# output.net
KiCad netlist of a schematic drawn in Altium Designer
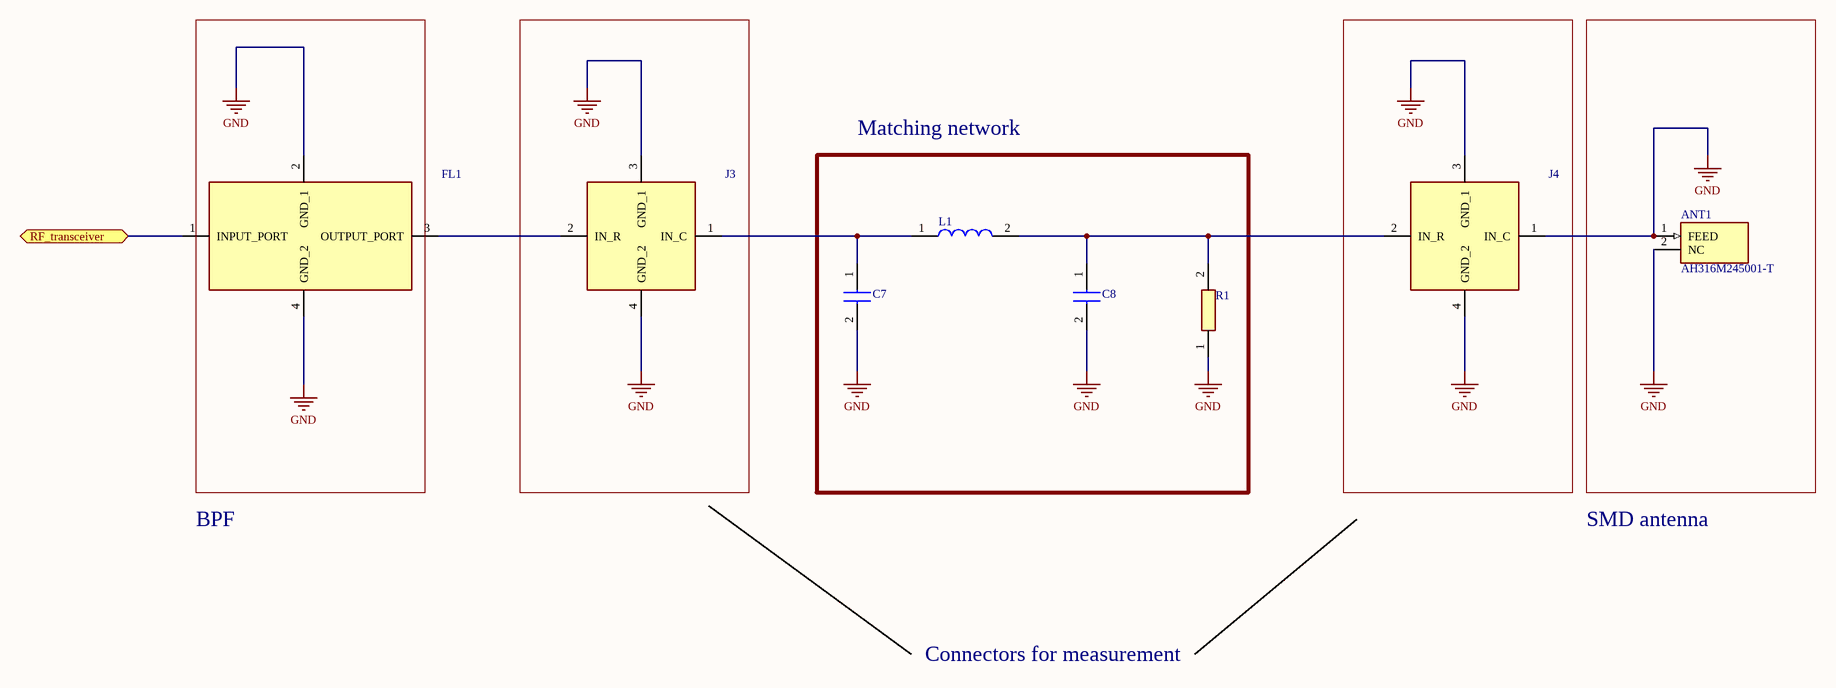
[diagram p0: output.SchDoc]

(export (version "E")
  (design (tool "Eeschema 10.0.6"))
  (components
    (comp (ref "ANT1")
      (value "AH316M245001-T")
      (footprint "SamacSys:ANTC3216X60N")
      (description "Antenna")
      (fields (field (name "MOUSER PART NUMBER") "963-AH316M245001-T"))
      (libsource (lib "*") (part "AH316M245001-T"))
    )
    (comp (ref "C7")
      (value "GRM1555C1HR50BA01D")
      (footprint "SamacSys:CAPC1005X55N")
      (description "Capacitor")
      (fields (field (name "MOUSER PART NUMBER") "81-GRM1555C1HR50BA1D"))
      (libsource (lib "*") (part "GRM1555C1HR50BA01D"))
    )
    (comp (ref "C8")
      (value "GRM1555C1HR50BA01D")
      (footprint "SamacSys:CAPC1005X55N")
      (description "Capacitor")
      (fields (field (name "MOUSER PART NUMBER") "81-GRM1555C1HR50BA1D"))
      (libsource (lib "*") (part "GRM1555C1HR50BA01D"))
    )
    (comp (ref "FL1")
      (value "DEA202450BT-1294D1-H")
      (footprint "SamacSys:DEA202450BT1294D1H")
      (description "Filter")
      (fields (field (name "MOUSER PART NUMBER") "810-DEA202450BT1294D"))
      (libsource (lib "SamacSys") (part "DEA202450BT-1294D1-H"))
    )
    (comp (ref "J3")
      (value "MM8030-2610RJ3")
      (footprint "SamacSys:MM80302610RJ3")
      (description "Connector")
      (fields (field (name "MOUSER2 PART NUMBER") "81-MM8030-2610RJ3"))
      (libsource (lib "SamacSys") (part "MM8030-2610RJ3"))
    )
    (comp (ref "J4")
      (value "MM8030-2610RJ3")
      (footprint "SamacSys:MM80302610RJ3")
      (description "Connector")
      (fields (field (name "MOUSER2 PART NUMBER") "81-MM8030-2610RJ3"))
      (libsource (lib "SamacSys") (part "MM8030-2610RJ3"))
    )
    (comp (ref "L1")
      (value "LQG15HS3N3S02D")
      (footprint "SamacSys:LQG15WH0N7B02D")
      (description "Inductor")
      (fields (field (name "MOUSER PART NUMBER") "81-LQG15HS3N3S02D"))
      (libsource (lib "SamacSys") (part "LQG15HS3N3S02D"))
    )
    (comp (ref "R1")
      (value "CH0402-50RGFPT")
      (footprint "SamacSys:RESC1006X63N")
      (description "Resistor")
      (fields (field (name "MOUSER PART NUMBER") "71-CH0402-50RGFPT"))
      (libsource (lib "*") (part "CH0402-50RGFPT"))
    )
  )
  (nets
    (net (code "1") (name "/RF_transceiver") (class "Default")
      (node (ref "FL1") (pin "1") (pinfunction "INPUT_PORT_1") (pintype "passive"))
    )
    (net (code "2") (name "GND") (class "Default")
      (node (ref "ANT1") (pin "1") (pinfunction "FEED_1") (pintype "input"))
      (node (ref "ANT1") (pin "2") (pinfunction "NC_2") (pintype "passive"))
      (node (ref "C7") (pin "2") (pinfunction "2_2") (pintype "passive"))
      (node (ref "C8") (pin "2") (pinfunction "2_2") (pintype "passive"))
      (node (ref "FL1") (pin "2") (pinfunction "GND_1_2") (pintype "passive"))
      (node (ref "FL1") (pin "4") (pinfunction "GND_2_4") (pintype "passive"))
      (node (ref "J3") (pin "3") (pinfunction "GND_1_3") (pintype "passive"))
      (node (ref "J3") (pin "4") (pinfunction "GND_2_4") (pintype "passive"))
      (node (ref "J4") (pin "1") (pinfunction "IN_C_1") (pintype "passive"))
      (node (ref "J4") (pin "3") (pinfunction "GND_1_3") (pintype "passive"))
      (node (ref "J4") (pin "4") (pinfunction "GND_2_4") (pintype "passive"))
      (node (ref "R1") (pin "1") (pinfunction "1_1") (pintype "passive"))
    )
    (net (code "3") (name "Net-(FL1-OUTPUT_PORT)") (class "Default")
      (node (ref "FL1") (pin "3") (pinfunction "OUTPUT_PORT_3") (pintype "passive"))
      (node (ref "J3") (pin "2") (pinfunction "IN_R_2") (pintype "passive"))
    )
    (net (code "4") (name "Net-(J3-IN_C)") (class "Default")
      (node (ref "C7") (pin "1") (pinfunction "1_1") (pintype "passive"))
      (node (ref "J3") (pin "1") (pinfunction "IN_C_1") (pintype "passive"))
      (node (ref "L1") (pin "1") (pinfunction "1_1") (pintype "passive"))
    )
    (net (code "5") (name "Net-(J4-IN_R)") (class "Default")
      (node (ref "C8") (pin "1") (pinfunction "1_1") (pintype "passive"))
      (node (ref "J4") (pin "2") (pinfunction "IN_R_2") (pintype "passive"))
      (node (ref "L1") (pin "2") (pinfunction "2_2") (pintype "passive"))
      (node (ref "R1") (pin "2") (pinfunction "2_2") (pintype "passive"))
    )
  )
)
